# USB.net
KiCad netlist of a schematic drawn in Altium Designer
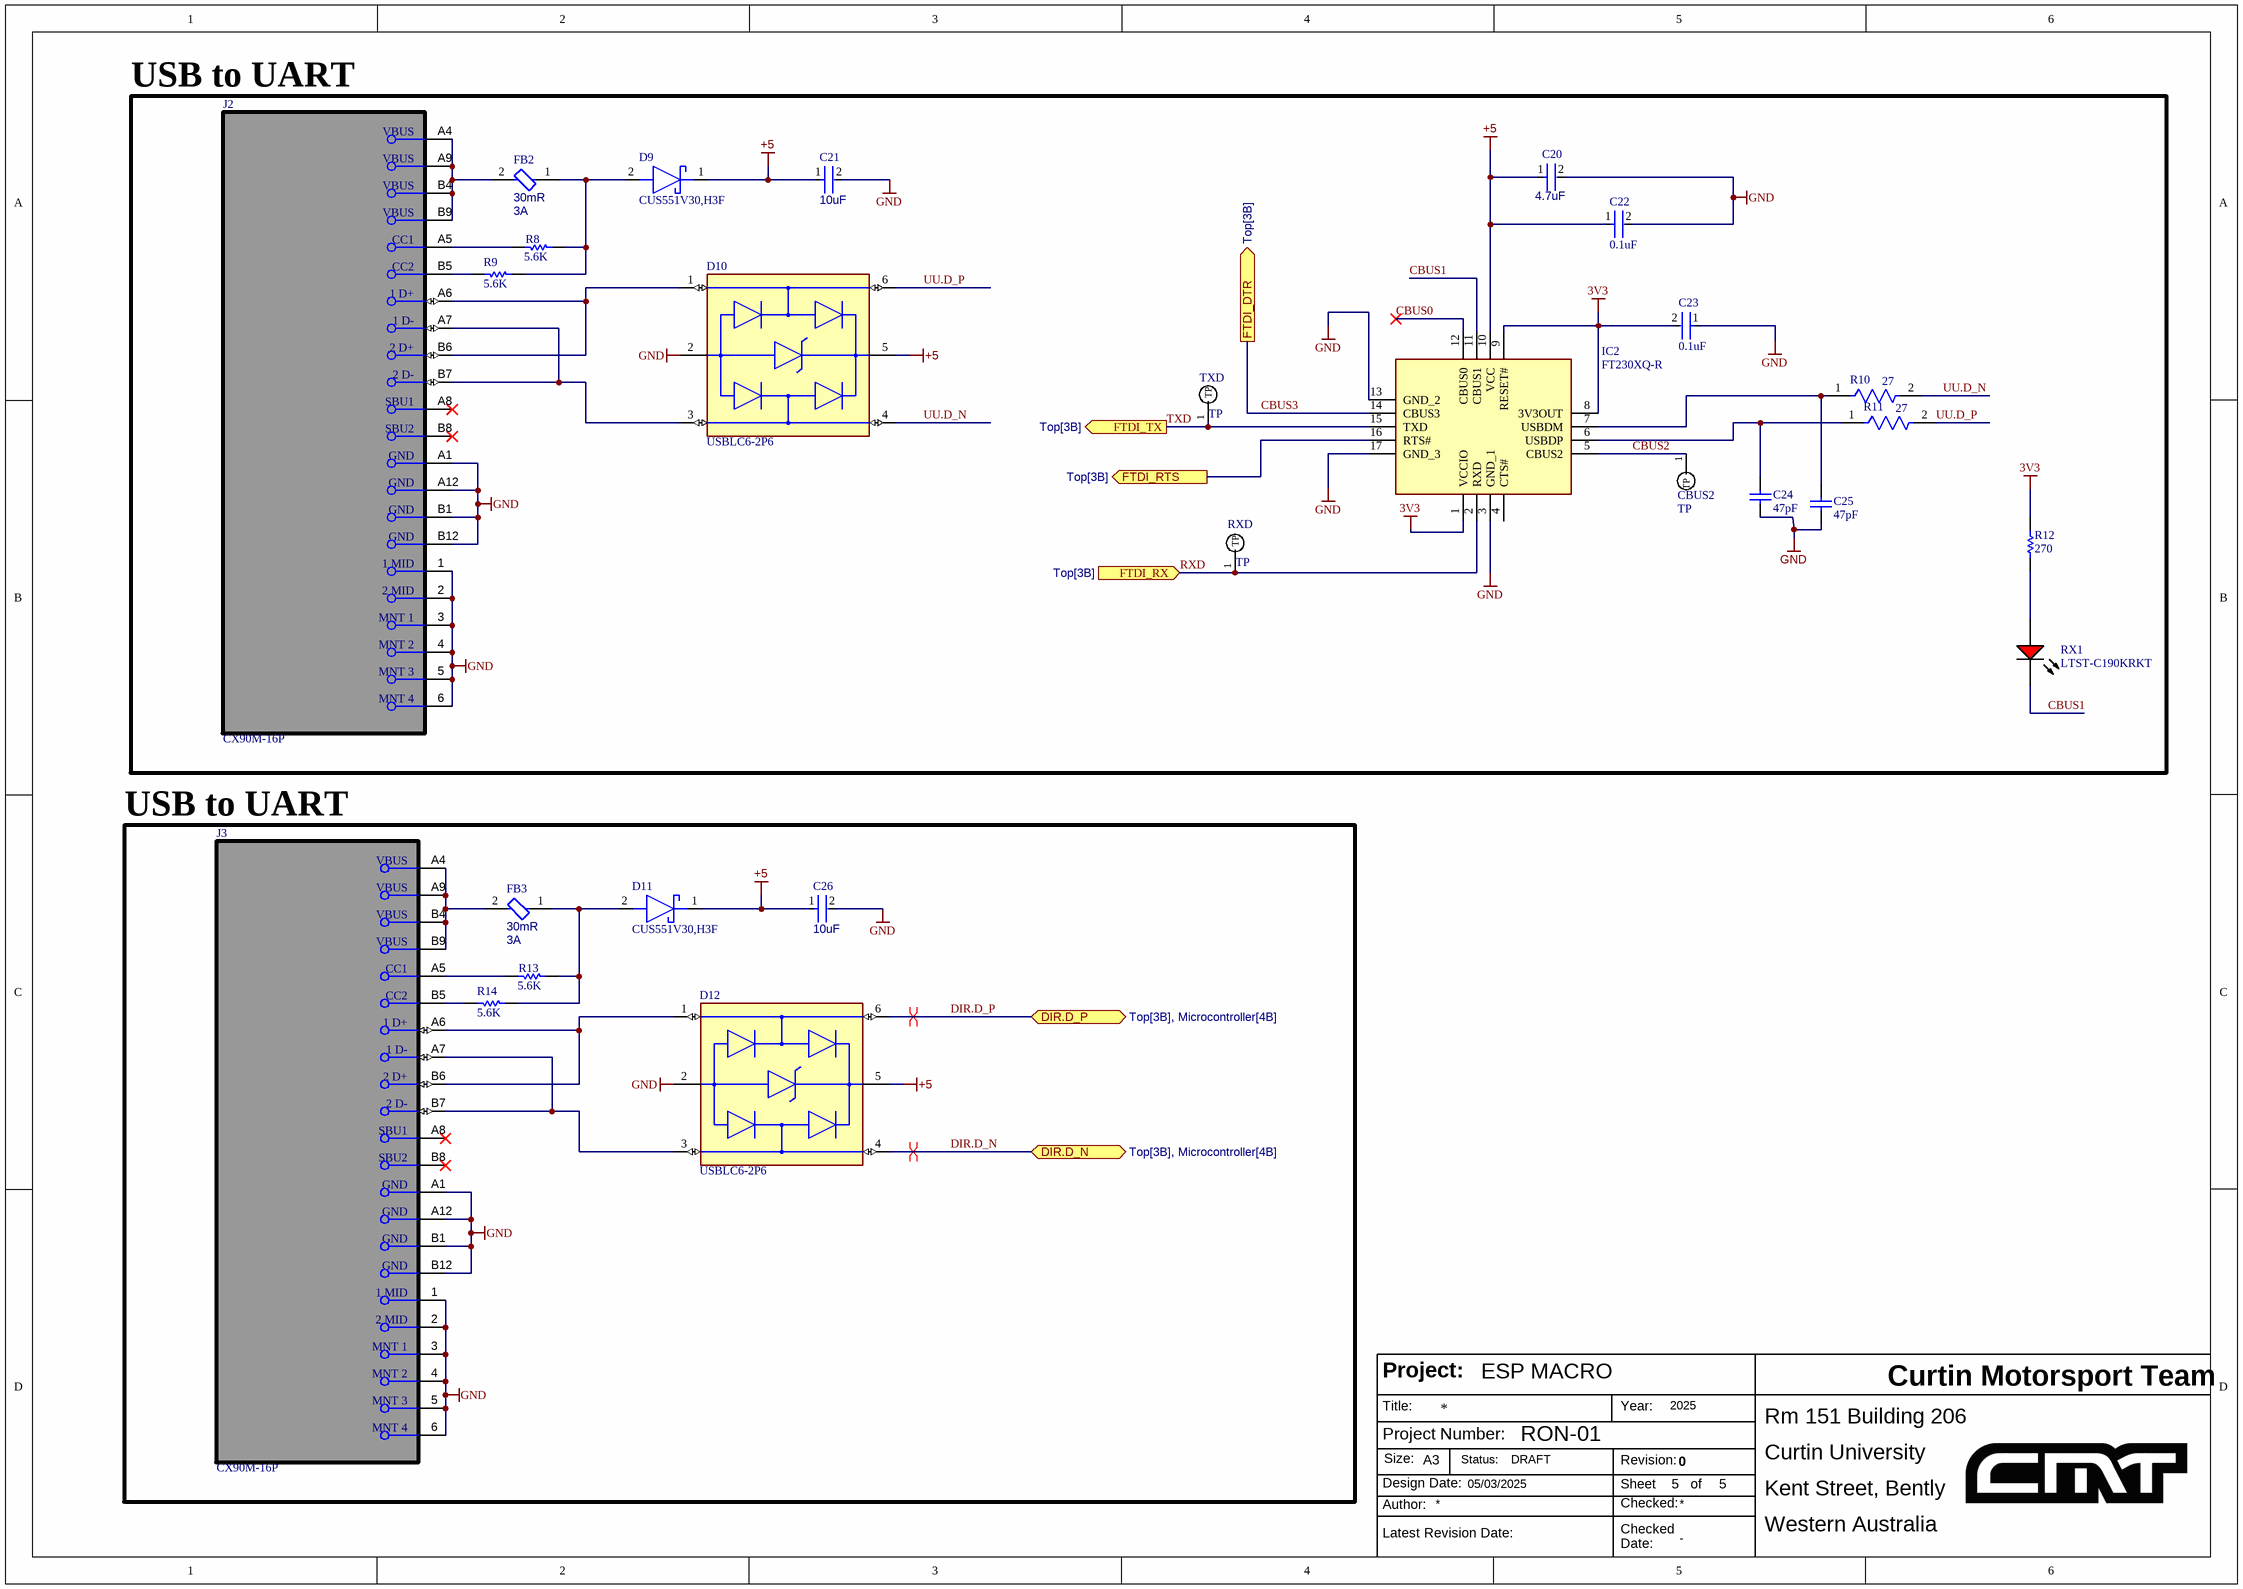
[diagram p0: USB.SchDoc]

(export (version "E")
  (design (tool "Eeschema 10.0.6"))
  (components
    (comp (ref "C20")
      (value "GRM188R61E475KE11D")
      (footprint "FP-GRM188-0_15-IPC_C")
      (description "Chip Multilayer Ceramic Capacitors for General Purpose, 0603, 4.7uF, X5R, 15%, 10%, 25V")
      (fields
        (field (name "CAPACITANCE") "4.7uF")
        (field (name "VOLTAGE") "25V")
        (field (name "TOLERANCE") "10%")
      )
      (libsource (lib "Altium Content Vault") (part "02cd4be3c70576c341d710602a673aa"))
    )
    (comp (ref "C21")
      (value "C1608X5R1E106M080AC")
      (footprint "FP-C1608-080-IPC_A")
      (description "CAP CER 10UF 25V X5R 0603")
      (fields (field (name "TOLERANCE") "20%") (field (name "CAPACITANCE") "10uF"))
      (libsource (lib "Altium Content Vault") (part "11868f565c42a9108669ba33697ecf6"))
    )
    (comp (ref "C22")
      (value "0.1uF")
      (footprint "FP-C0603C-CF-MFG")
      (description "CAP CER 0.1UF 50V X7R 0603")
      (fields (field (name "TOLERANCE") "0.1") (field (name "MANUFACTURER") "KEMET"))
      (libsource (lib "Altium Content Vault") (part "b4654b650e69147ec39a6b967a45e02"))
    )
    (comp (ref "C23")
      (value "0.1uF")
      (footprint "FP-C0603C-CF-MFG")
      (description "CAP CER 0.1UF 50V X7R 0603")
      (fields (field (name "TOLERANCE") "0.1") (field (name "MANUFACTURER") "KEMET"))
      (libsource (lib "Altium Content Vault") (part "b4654b650e69147ec39a6b967a45e02"))
    )
    (comp (ref "C24")
      (value "47pF")
      (footprint "CAPC1608X90X35NL10T15")
      (fields (field (name "MANUFACTURER") "Murata") (field (name "PART NUMBER") "GRM1885C1H470JA01D"))
      (libsource (lib "Altium Content Vault") (part "CAP"))
    )
    (comp (ref "C25")
      (value "47pF")
      (footprint "CAPC1608X90X35NL10T15")
      (fields (field (name "MANUFACTURER") "Murata") (field (name "PART NUMBER") "GRM1885C1H470JA01D"))
      (libsource (lib "Altium Content Vault") (part "CAP"))
    )
    (comp (ref "C26")
      (value "C1608X5R1E106M080AC")
      (footprint "FP-C1608-080-IPC_A")
      (description "CAP CER 10UF 25V X5R 0603")
      (fields (field (name "TOLERANCE") "20%") (field (name "CAPACITANCE") "10uF"))
      (libsource (lib "Altium Content Vault") (part "11868f565c42a9108669ba33697ecf6"))
    )
    (comp (ref "CBUS2")
      (value "TP")
      (footprint "TestPad")
      (libsource (lib "StrainComponents") (part "Test Points"))
    )
    (comp (ref "D9")
      (value "CUS551V30,H3F")
      (footprint "1SS357TPH3F")
      (description "Schottky Diode")
      (fields (field (name "MOUSER PART NUMBER") "757-CUS551V30H3F"))
      (libsource (lib "Curtin Motorsport Team") (part "CUS551V30,H3F"))
    )
    (comp (ref "D10")
      (value "USBLC6-2P6")
      (footprint "FP-SOT-666-MFG")
      (description "TVS DIODE 5.25V 17V SOT666")
      (libsource (lib "Altium Content Vault") (part "c871e55f7e3243d341edbd671b98d92"))
    )
    (comp (ref "D11")
      (value "CUS551V30,H3F")
      (footprint "1SS357TPH3F")
      (description "Schottky Diode")
      (fields (field (name "MOUSER PART NUMBER") "757-CUS551V30H3F"))
      (libsource (lib "Curtin Motorsport Team") (part "CUS551V30,H3F"))
    )
    (comp (ref "D12")
      (value "USBLC6-2P6")
      (footprint "FP-SOT-666-MFG")
      (description "TVS DIODE 5.25V 17V SOT666")
      (libsource (lib "Altium Content Vault") (part "c871e55f7e3243d341edbd671b98d92"))
    )
    (comp (ref "FB2")
      (value "BLM21PG121SN1D")
      (footprint "FP-BLM21-0_2-t0_85-e0_5-d-IPC_B")
      (description "Ferrite Beads Multi-Layer 120Ohm 25% 100MHz 3A 30mOhm DCR 0805 Paper T/R")
      (fields (field (name "DC RESISTANCE (DCR)") "30mR") (field (name "CURRENT RATING") "3A"))
      (libsource (lib "Curtin Motorsport Team") (part "5f30dd21d616792df468990f7003faa"))
    )
    (comp (ref "FB3")
      (value "BLM21PG121SN1D")
      (footprint "FP-BLM21-0_2-t0_85-e0_5-d-IPC_B")
      (description "Ferrite Beads Multi-Layer 120Ohm 25% 100MHz 3A 30mOhm DCR 0805 Paper T/R")
      (fields (field (name "DC RESISTANCE (DCR)") "30mR") (field (name "CURRENT RATING") "3A"))
      (libsource (lib "Curtin Motorsport Team") (part "5f30dd21d616792df468990f7003faa"))
    )
    (comp (ref "IC2")
      (value "FT230XQ-R")
      (footprint "QFN65P400X400X80-17N")
      (description "Integrated Circuit")
      (fields (field (name "MOUSER PART NUMBER") "895-FT230XQ-R"))
      (libsource (lib "Curtin Motorsport Team") (part "FT230XQ-R"))
    )
    (comp (ref "J2")
      (value "CX90M-16P")
      (footprint "FP-CX90M-16P-MFG")
      (description "USB Connector, USB Type C, USB 2.0, Receptacle, 16 Ways, Surface Mount, Right Angle")
      (libsource (lib "Curtin Motorsport Team") (part "6b7e9819a715c2d1d3babe584a73dea"))
    )
    (comp (ref "J3")
      (value "CX90M-16P")
      (footprint "FP-CX90M-16P-MFG")
      (description "USB Connector, USB Type C, USB 2.0, Receptacle, 16 Ways, Surface Mount, Right Angle")
      (libsource (lib "Curtin Motorsport Team") (part "6b7e9819a715c2d1d3babe584a73dea"))
    )
    (comp (ref "R8")
      (value "5.6K")
      (footprint "RESC1609X50X30NL10T20")
      (fields (field (name "PART NUMBER") "CRCW060356K0FKEA") (field (name "MANUFACTURER") "Vishay Dale"))
      (libsource (lib "Altium Content Vault") (part "RES"))
    )
    (comp (ref "R9")
      (value "5.6K")
      (footprint "RESC1609X50X30NL10T20")
      (fields (field (name "PART NUMBER") "CRCW060356K0FKEA") (field (name "MANUFACTURER") "Vishay Dale"))
      (libsource (lib "Altium Content Vault") (part "RES"))
    )
    (comp (ref "R10")
      (value "27")
      (footprint "FP-ERJ3EK-IPC_B")
      (description "RES SMD 27 OHM 1% 1/10W 0603")
      (fields (field (name "TOLERANCE") "1%"))
      (libsource (lib "Altium Content Vault") (part "1029c3af85768c4190bb7ad29bc67b5"))
    )
    (comp (ref "R11")
      (value "27")
      (footprint "FP-ERJ3EK-IPC_B")
      (description "RES SMD 27 OHM 1% 1/10W 0603")
      (fields (field (name "TOLERANCE") "1%"))
      (libsource (lib "Altium Content Vault") (part "1029c3af85768c4190bb7ad29bc67b5"))
    )
    (comp (ref "R12")
      (value "270")
      (footprint "RESC1609X50X30NL10T20")
      (fields (field (name "PART NUMBER") "CRCW060356K0FKEA") (field (name "MANUFACTURER") "Vishay Dale"))
      (libsource (lib "Altium Content Vault") (part "RES"))
    )
    (comp (ref "R13")
      (value "5.6K")
      (footprint "RESC1609X50X30NL10T20")
      (fields (field (name "PART NUMBER") "CRCW060356K0FKEA") (field (name "MANUFACTURER") "Vishay Dale"))
      (libsource (lib "Altium Content Vault") (part "RES"))
    )
    (comp (ref "R14")
      (value "5.6K")
      (footprint "RESC1609X50X30NL10T20")
      (fields (field (name "PART NUMBER") "CRCW060356K0FKEA") (field (name "MANUFACTURER") "Vishay Dale"))
      (libsource (lib "Altium Content Vault") (part "RES"))
    )
    (comp (ref "RX1")
      (value "LTST-C190KRKT")
      (footprint "LTST-C191KRKT_V")
      (description "LED Uni-Color Red, 62.5 mW, 25 mA, -30 to 85 degC, 2-Pin SMD, RoHS, Tape and Reel")
      (fields (field (name "POWER") "75mW") (field (name "MANUFACTURER") "Lite-On"))
      (libsource (lib "Curtin Motorsport Team") (part "LED-RED-AK-2"))
    )
    (comp (ref "RXD")
      (value "TP")
      (footprint "TestPad")
      (libsource (lib "StrainComponents") (part "Test Points"))
    )
    (comp (ref "TXD")
      (value "TP")
      (footprint "TestPad")
      (libsource (lib "StrainComponents") (part "Test Points"))
    )
  )
  (nets
    (net (code "1") (name "+5") (class "Default")
      (node (ref "C20") (pin "1") (pinfunction "1_1") (pintype "passive"))
      (node (ref "C21") (pin "1") (pinfunction "1_1") (pintype "passive"))
      (node (ref "C22") (pin "1") (pinfunction "1_1") (pintype "passive"))
      (node (ref "C26") (pin "1") (pinfunction "1_1") (pintype "passive"))
      (node (ref "D10") (pin "5") (pinfunction "VBUS_5") (pintype "power_in"))
      (node (ref "D11") (pin "1") (pinfunction "K_1") (pintype "passive"))
      (node (ref "D12") (pin "5") (pinfunction "VBUS_5") (pintype "power_in"))
      (node (ref "D9") (pin "1") (pinfunction "K_1") (pintype "passive"))
      (node (ref "IC2") (pin "10") (pinfunction "VCC_10") (pintype "passive"))
    )
    (net (code "2") (name "/CBUS0") (class "Default")
      (node (ref "IC2") (pin "12") (pinfunction "CBUS0_12") (pintype "passive+no_connect"))
    )
    (net (code "3") (name "/CBUS1") (class "Default")
      (node (ref "IC2") (pin "11") (pinfunction "CBUS1_11") (pintype "passive"))
      (node (ref "RX1") (pin "2") (pinfunction "K_2") (pintype "passive"))
    )
    (net (code "4") (name "/CBUS2") (class "Default")
      (node (ref "CBUS2") (pin "1") (pinfunction "TP_1") (pintype "passive"))
      (node (ref "IC2") (pin "5") (pinfunction "CBUS2_5") (pintype "passive"))
    )
    (net (code "5") (name "/CBUS3") (class "Default")
      (node (ref "IC2") (pin "14") (pinfunction "CBUS3_14") (pintype "passive"))
    )
    (net (code "6") (name "/DIR.D_N") (class "Default")
      (node (ref "D12") (pin "4") (pinfunction "I/O2_4") (pintype "bidirectional"))
    )
    (net (code "7") (name "/DIR.D_P") (class "Default")
      (node (ref "D12") (pin "6") (pinfunction "I/O1_6") (pintype "bidirectional"))
    )
    (net (code "8") (name "/FTDI_RTS") (class "Default")
      (node (ref "IC2") (pin "16") (pinfunction "RTS#_16") (pintype "passive"))
    )
    (net (code "9") (name "/RXD") (class "Default")
      (node (ref "IC2") (pin "2") (pinfunction "RXD_2") (pintype "passive"))
      (node (ref "RXD") (pin "1") (pinfunction "TP_1") (pintype "passive"))
    )
    (net (code "10") (name "/TXD") (class "Default")
      (node (ref "IC2") (pin "15") (pinfunction "TXD_15") (pintype "passive"))
      (node (ref "TXD") (pin "1") (pinfunction "TP_1") (pintype "passive"))
    )
    (net (code "11") (name "/UU.D_N") (class "Default")
      (node (ref "D10") (pin "4") (pinfunction "I/O2_4") (pintype "bidirectional"))
      (node (ref "R10") (pin "2") (pinfunction "2_2") (pintype "passive"))
    )
    (net (code "12") (name "/UU.D_P") (class "Default")
      (node (ref "D10") (pin "6") (pinfunction "I/O1_6") (pintype "bidirectional"))
      (node (ref "R11") (pin "2") (pinfunction "2_2") (pintype "passive"))
    )
    (net (code "13") (name "3V3") (class "Default")
      (node (ref "C23") (pin "2") (pinfunction "2_2") (pintype "passive"))
      (node (ref "IC2") (pin "1") (pinfunction "VCCIO_1") (pintype "passive"))
      (node (ref "IC2") (pin "8") (pinfunction "3V3OUT_8") (pintype "passive"))
      (node (ref "IC2") (pin "9") (pinfunction "RESET#_9") (pintype "passive"))
      (node (ref "R12") (pin "2") (pinfunction "2_2") (pintype "passive"))
    )
    (net (code "14") (name "GND") (class "Default")
      (node (ref "C20") (pin "2") (pinfunction "2_2") (pintype "passive"))
      (node (ref "C21") (pin "2") (pinfunction "2_2") (pintype "passive"))
      (node (ref "C22") (pin "2") (pinfunction "2_2") (pintype "passive"))
      (node (ref "C23") (pin "1") (pinfunction "1_1") (pintype "passive"))
      (node (ref "C24") (pin "1") (pinfunction "1_1") (pintype "passive"))
      (node (ref "C25") (pin "1") (pinfunction "1_1") (pintype "passive"))
      (node (ref "C26") (pin "2") (pinfunction "2_2") (pintype "passive"))
      (node (ref "D10") (pin "2") (pinfunction "GND_2") (pintype "power_in"))
      (node (ref "D12") (pin "2") (pinfunction "GND_2") (pintype "power_in"))
      (node (ref "IC2") (pin "13") (pinfunction "GND_2_13") (pintype "passive"))
      (node (ref "IC2") (pin "17") (pinfunction "GND_3_17") (pintype "passive"))
      (node (ref "IC2") (pin "3") (pinfunction "GND_1_3") (pintype "passive"))
      (node (ref "J2") (pin "1") (pinfunction "1_MID_1") (pintype "passive"))
      (node (ref "J2") (pin "2") (pinfunction "2_MID_2") (pintype "passive"))
      (node (ref "J2") (pin "3") (pinfunction "MNT_1_3") (pintype "passive"))
      (node (ref "J2") (pin "4") (pinfunction "MNT_2_4") (pintype "passive"))
      (node (ref "J2") (pin "5") (pinfunction "MNT_3_5") (pintype "passive"))
      (node (ref "J2") (pin "6") (pinfunction "MNT_4_6") (pintype "passive"))
      (node (ref "J2") (pin "A1") (pinfunction "GND_A1") (pintype "power_in"))
      (node (ref "J2") (pin "A12") (pinfunction "GND_A12") (pintype "power_in"))
      (node (ref "J2") (pin "B1") (pinfunction "GND_B1") (pintype "power_in"))
      (node (ref "J2") (pin "B12") (pinfunction "GND_B12") (pintype "power_in"))
      (node (ref "J3") (pin "1") (pinfunction "1_MID_1") (pintype "passive"))
      (node (ref "J3") (pin "2") (pinfunction "2_MID_2") (pintype "passive"))
      (node (ref "J3") (pin "3") (pinfunction "MNT_1_3") (pintype "passive"))
      (node (ref "J3") (pin "4") (pinfunction "MNT_2_4") (pintype "passive"))
      (node (ref "J3") (pin "5") (pinfunction "MNT_3_5") (pintype "passive"))
      (node (ref "J3") (pin "6") (pinfunction "MNT_4_6") (pintype "passive"))
      (node (ref "J3") (pin "A1") (pinfunction "GND_A1") (pintype "power_in"))
      (node (ref "J3") (pin "A12") (pinfunction "GND_A12") (pintype "power_in"))
      (node (ref "J3") (pin "B1") (pinfunction "GND_B1") (pintype "power_in"))
      (node (ref "J3") (pin "B12") (pinfunction "GND_B12") (pintype "power_in"))
    )
    (net (code "15") (name "Net-(D9-A)") (class "Default")
      (node (ref "D9") (pin "2") (pinfunction "A_2") (pintype "passive"))
      (node (ref "FB2") (pin "1") (pinfunction "1_1") (pintype "passive"))
      (node (ref "R8") (pin "1") (pinfunction "1_1") (pintype "passive"))
      (node (ref "R9") (pin "2") (pinfunction "2_2") (pintype "passive"))
    )
    (net (code "16") (name "Net-(D11-A)") (class "Default")
      (node (ref "D11") (pin "2") (pinfunction "A_2") (pintype "passive"))
      (node (ref "FB3") (pin "1") (pinfunction "1_1") (pintype "passive"))
      (node (ref "R13") (pin "1") (pinfunction "1_1") (pintype "passive"))
      (node (ref "R14") (pin "2") (pinfunction "2_2") (pintype "passive"))
    )
    (net (code "17") (name "Net-(FB2-Pad2)") (class "Default")
      (node (ref "FB2") (pin "2") (pinfunction "2_2") (pintype "passive"))
      (node (ref "J2") (pin "A4") (pinfunction "VBUS_A4") (pintype "power_in"))
      (node (ref "J2") (pin "A9") (pinfunction "VBUS_A9") (pintype "power_in"))
      (node (ref "J2") (pin "B4") (pinfunction "VBUS_B4") (pintype "power_in"))
      (node (ref "J2") (pin "B9") (pinfunction "VBUS_B9") (pintype "power_in"))
    )
    (net (code "18") (name "Net-(FB3-Pad2)") (class "Default")
      (node (ref "FB3") (pin "2") (pinfunction "2_2") (pintype "passive"))
      (node (ref "J3") (pin "A4") (pinfunction "VBUS_A4") (pintype "power_in"))
      (node (ref "J3") (pin "A9") (pinfunction "VBUS_A9") (pintype "power_in"))
      (node (ref "J3") (pin "B4") (pinfunction "VBUS_B4") (pintype "power_in"))
      (node (ref "J3") (pin "B9") (pinfunction "VBUS_B9") (pintype "power_in"))
    )
    (net (code "19") (name "Net-(IC2-USBDM)") (class "Default")
      (node (ref "C25") (pin "2") (pinfunction "2_2") (pintype "passive"))
      (node (ref "IC2") (pin "7") (pinfunction "USBDM_7") (pintype "passive"))
      (node (ref "R10") (pin "1") (pinfunction "1_1") (pintype "passive"))
    )
    (net (code "20") (name "Net-(IC2-USBDP)") (class "Default")
      (node (ref "C24") (pin "2") (pinfunction "2_2") (pintype "passive"))
      (node (ref "IC2") (pin "6") (pinfunction "USBDP_6") (pintype "passive"))
      (node (ref "R11") (pin "1") (pinfunction "1_1") (pintype "passive"))
    )
    (net (code "21") (name "Net-(J2-1_D+)") (class "Default")
      (node (ref "D10") (pin "1") (pinfunction "I/O1_1") (pintype "bidirectional"))
      (node (ref "J2") (pin "A6") (pinfunction "1_D+_A6") (pintype "bidirectional"))
      (node (ref "J2") (pin "B6") (pinfunction "2_D+_B6") (pintype "bidirectional"))
    )
    (net (code "22") (name "Net-(J2-1_D-)") (class "Default")
      (node (ref "D10") (pin "3") (pinfunction "I/O2_3") (pintype "bidirectional"))
      (node (ref "J2") (pin "A7") (pinfunction "1_D-_A7") (pintype "bidirectional"))
      (node (ref "J2") (pin "B7") (pinfunction "2_D-_B7") (pintype "bidirectional"))
    )
    (net (code "23") (name "Net-(J2-CC1)") (class "Default")
      (node (ref "J2") (pin "A5") (pinfunction "CC1_A5") (pintype "passive"))
      (node (ref "R8") (pin "2") (pinfunction "2_2") (pintype "passive"))
    )
    (net (code "24") (name "Net-(J2-CC2)") (class "Default")
      (node (ref "J2") (pin "B5") (pinfunction "CC2_B5") (pintype "passive"))
      (node (ref "R9") (pin "1") (pinfunction "1_1") (pintype "passive"))
    )
    (net (code "25") (name "Net-(J3-1_D+)") (class "Default")
      (node (ref "D12") (pin "1") (pinfunction "I/O1_1") (pintype "bidirectional"))
      (node (ref "J3") (pin "A6") (pinfunction "1_D+_A6") (pintype "bidirectional"))
      (node (ref "J3") (pin "B6") (pinfunction "2_D+_B6") (pintype "bidirectional"))
    )
    (net (code "26") (name "Net-(J3-1_D-)") (class "Default")
      (node (ref "D12") (pin "3") (pinfunction "I/O2_3") (pintype "bidirectional"))
      (node (ref "J3") (pin "A7") (pinfunction "1_D-_A7") (pintype "bidirectional"))
      (node (ref "J3") (pin "B7") (pinfunction "2_D-_B7") (pintype "bidirectional"))
    )
    (net (code "27") (name "Net-(J3-CC1)") (class "Default")
      (node (ref "J3") (pin "A5") (pinfunction "CC1_A5") (pintype "passive"))
      (node (ref "R13") (pin "2") (pinfunction "2_2") (pintype "passive"))
    )
    (net (code "28") (name "Net-(J3-CC2)") (class "Default")
      (node (ref "J3") (pin "B5") (pinfunction "CC2_B5") (pintype "passive"))
      (node (ref "R14") (pin "1") (pinfunction "1_1") (pintype "passive"))
    )
    (net (code "29") (name "Net-(RX1-A)") (class "Default")
      (node (ref "R12") (pin "1") (pinfunction "1_1") (pintype "passive"))
      (node (ref "RX1") (pin "1") (pinfunction "A_1") (pintype "passive"))
    )
    (net (code "30") (name "unconnected-(IC2-CTS#-Pad4)") (class "Default")
      (node (ref "IC2") (pin "4") (pinfunction "CTS#_4") (pintype "passive"))
    )
    (net (code "31") (name "unconnected-(J2-SBU1-PadA8)") (class "Default")
      (node (ref "J2") (pin "A8") (pinfunction "SBU1_A8") (pintype "passive+no_connect"))
    )
    (net (code "32") (name "unconnected-(J2-SBU2-PadB8)") (class "Default")
      (node (ref "J2") (pin "B8") (pinfunction "SBU2_B8") (pintype "passive+no_connect"))
    )
    (net (code "33") (name "unconnected-(J3-SBU1-PadA8)") (class "Default")
      (node (ref "J3") (pin "A8") (pinfunction "SBU1_A8") (pintype "passive+no_connect"))
    )
    (net (code "34") (name "unconnected-(J3-SBU2-PadB8)") (class "Default")
      (node (ref "J3") (pin "B8") (pinfunction "SBU2_B8") (pintype "passive+no_connect"))
    )
  )
)
